# LVDS_UART.net
KiCad netlist of a schematic drawn in Altium Designer
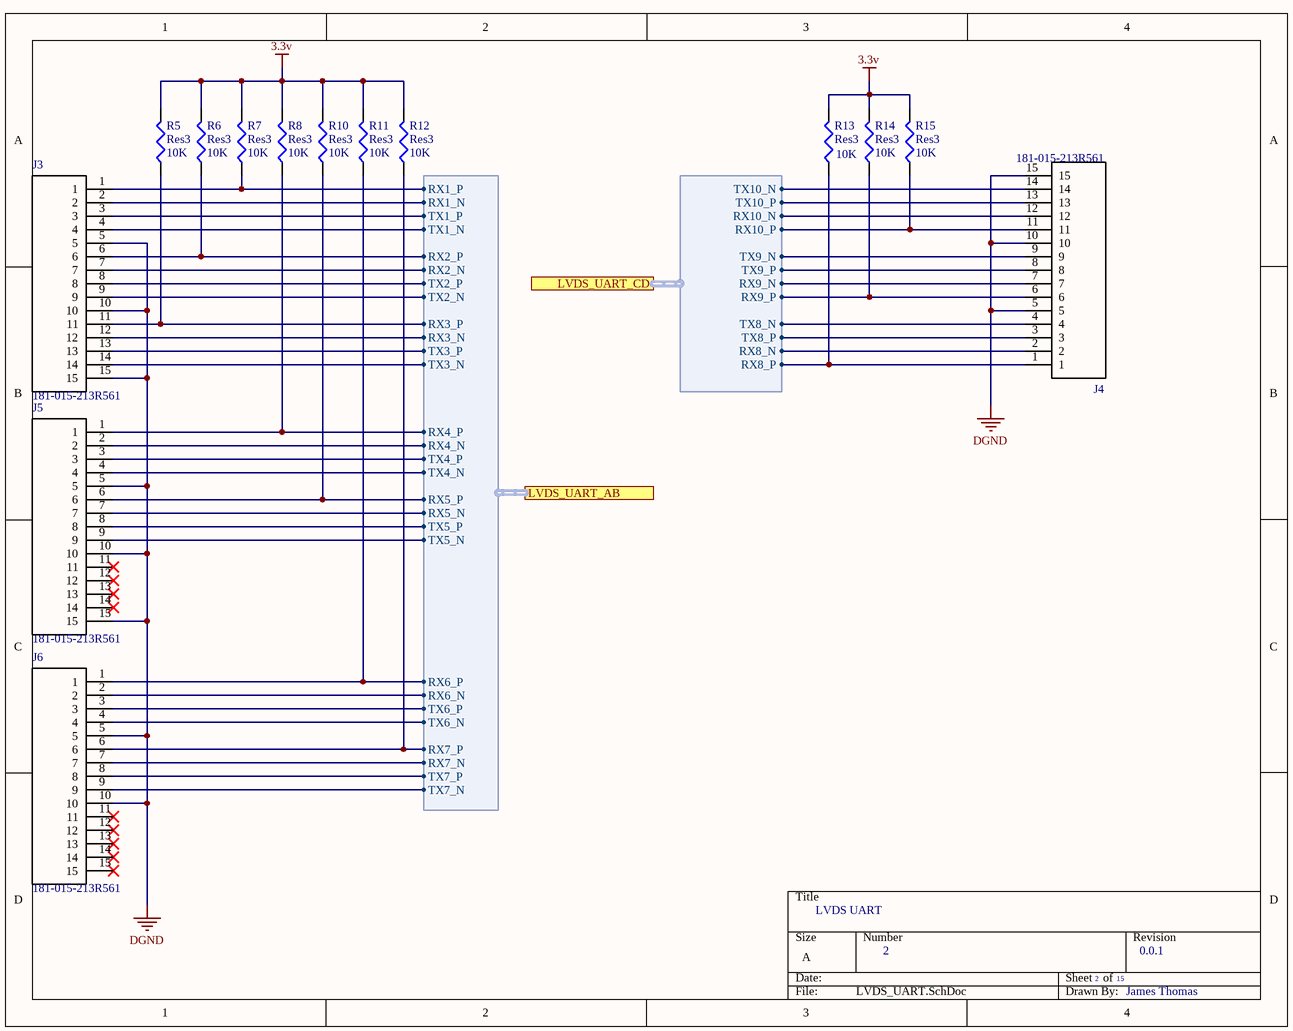
[diagram p0: LVDS_UART.SchDoc]

(export (version "E")
  (design (tool "Eeschema 10.0.6"))
  (components
    (comp (ref "J3")
      (value "181-015-213R561")
      (footprint "*NORCOMP_181-015-213R561")
      (description "15 Position D-Sub, High Density Receptacle, Female Sockets Connector")
      (fields (field (name "MF") "NorComp Inc."))
      (libsource (lib "Components") (part "181-015-213R561"))
    )
    (comp (ref "J4")
      (value "181-015-213R561")
      (footprint "*NORCOMP_181-015-213R561")
      (description "15 Position D-Sub, High Density Receptacle, Female Sockets Connector")
      (fields (field (name "MF") "NorComp Inc."))
      (libsource (lib "Components") (part "181-015-213R561"))
    )
    (comp (ref "J5")
      (value "181-015-213R561")
      (footprint "*NORCOMP_181-015-213R561")
      (description "15 Position D-Sub, High Density Receptacle, Female Sockets Connector")
      (fields (field (name "MF") "NorComp Inc."))
      (libsource (lib "Components") (part "181-015-213R561"))
    )
    (comp (ref "J6")
      (value "181-015-213R561")
      (footprint "*NORCOMP_181-015-213R561")
      (description "15 Position D-Sub, High Density Receptacle, Female Sockets Connector")
      (fields (field (name "MF") "NorComp Inc."))
      (libsource (lib "Components") (part "181-015-213R561"))
    )
    (comp (ref "R5")
      (value "Res3")
      (footprint "J1-0603")
      (description "Resistor")
      (fields (field (name "ALTIUM_VALUE") "10K") (field (name "PUBLISHER") "Altium Limited"))
      (libsource (lib "Miscellaneous Devices") (part "Res3"))
    )
    (comp (ref "R6")
      (value "Res3")
      (footprint "J1-0603")
      (description "Resistor")
      (fields (field (name "ALTIUM_VALUE") "10K") (field (name "PUBLISHER") "Altium Limited"))
      (libsource (lib "Miscellaneous Devices") (part "Res3"))
    )
    (comp (ref "R7")
      (value "Res3")
      (footprint "J1-0603")
      (description "Resistor")
      (fields (field (name "ALTIUM_VALUE") "10K") (field (name "PUBLISHER") "Altium Limited"))
      (libsource (lib "Miscellaneous Devices") (part "Res3"))
    )
    (comp (ref "R8")
      (value "Res3")
      (footprint "J1-0603")
      (description "Resistor")
      (fields (field (name "ALTIUM_VALUE") "10K") (field (name "PUBLISHER") "Altium Limited"))
      (libsource (lib "Miscellaneous Devices") (part "Res3"))
    )
    (comp (ref "R10")
      (value "Res3")
      (footprint "J1-0603")
      (description "Resistor")
      (fields (field (name "ALTIUM_VALUE") "10K") (field (name "PUBLISHER") "Altium Limited"))
      (libsource (lib "Miscellaneous Devices") (part "Res3"))
    )
    (comp (ref "R11")
      (value "Res3")
      (footprint "J1-0603")
      (description "Resistor")
      (fields (field (name "ALTIUM_VALUE") "10K") (field (name "PUBLISHER") "Altium Limited"))
      (libsource (lib "Miscellaneous Devices") (part "Res3"))
    )
    (comp (ref "R12")
      (value "Res3")
      (footprint "J1-0603")
      (description "Resistor")
      (fields (field (name "ALTIUM_VALUE") "10K") (field (name "PUBLISHER") "Altium Limited"))
      (libsource (lib "Miscellaneous Devices") (part "Res3"))
    )
    (comp (ref "R13")
      (value "Res3")
      (footprint "J1-0603")
      (description "Resistor")
      (fields (field (name "ALTIUM_VALUE") "10K") (field (name "PUBLISHER") "Altium Limited"))
      (libsource (lib "Miscellaneous Devices") (part "Res3"))
    )
    (comp (ref "R14")
      (value "Res3")
      (footprint "J1-0603")
      (description "Resistor")
      (fields (field (name "ALTIUM_VALUE") "10K") (field (name "PUBLISHER") "Altium Limited"))
      (libsource (lib "Miscellaneous Devices") (part "Res3"))
    )
    (comp (ref "R15")
      (value "Res3")
      (footprint "J1-0603")
      (description "Resistor")
      (fields (field (name "ALTIUM_VALUE") "10K") (field (name "PUBLISHER") "Altium Limited"))
      (libsource (lib "Miscellaneous Devices") (part "Res3"))
    )
  )
  (nets
    (net (code "3") (name "/RX1_N") (class "Default")
      (node (ref "J3") (pin "2") (pinfunction "2_2") (pintype "passive"))
    )
    (net (code "4") (name "/RX1_P") (class "Default")
      (node (ref "J3") (pin "1") (pinfunction "1_1") (pintype "passive"))
      (node (ref "R7") (pin "1") (pinfunction "1_1") (pintype "passive"))
    )
    (net (code "5") (name "/RX2_N") (class "Default")
      (node (ref "J3") (pin "7") (pinfunction "7_7") (pintype "passive"))
    )
    (net (code "6") (name "/RX2_P") (class "Default")
      (node (ref "J3") (pin "6") (pinfunction "6_6") (pintype "passive"))
      (node (ref "R6") (pin "1") (pinfunction "1_1") (pintype "passive"))
    )
    (net (code "7") (name "/RX3_N") (class "Default")
      (node (ref "J3") (pin "12") (pinfunction "12_12") (pintype "passive"))
    )
    (net (code "8") (name "/RX3_P") (class "Default")
      (node (ref "J3") (pin "11") (pinfunction "11_11") (pintype "passive"))
      (node (ref "R5") (pin "1") (pinfunction "1_1") (pintype "passive"))
    )
    (net (code "9") (name "/RX4_N") (class "Default")
      (node (ref "J5") (pin "2") (pinfunction "2_2") (pintype "passive"))
    )
    (net (code "10") (name "/RX4_P") (class "Default")
      (node (ref "J5") (pin "1") (pinfunction "1_1") (pintype "passive"))
      (node (ref "R8") (pin "1") (pinfunction "1_1") (pintype "passive"))
    )
    (net (code "11") (name "/RX5_N") (class "Default")
      (node (ref "J5") (pin "7") (pinfunction "7_7") (pintype "passive"))
    )
    (net (code "12") (name "/RX5_P") (class "Default")
      (node (ref "J5") (pin "6") (pinfunction "6_6") (pintype "passive"))
      (node (ref "R10") (pin "1") (pinfunction "1_1") (pintype "passive"))
    )
    (net (code "13") (name "/RX6_N") (class "Default")
      (node (ref "J6") (pin "2") (pinfunction "2_2") (pintype "passive"))
    )
    (net (code "14") (name "/RX6_P") (class "Default")
      (node (ref "J6") (pin "1") (pinfunction "1_1") (pintype "passive"))
      (node (ref "R11") (pin "1") (pinfunction "1_1") (pintype "passive"))
    )
    (net (code "15") (name "/RX7_N") (class "Default")
      (node (ref "J6") (pin "7") (pinfunction "7_7") (pintype "passive"))
    )
    (net (code "16") (name "/RX7_P") (class "Default")
      (node (ref "J6") (pin "6") (pinfunction "6_6") (pintype "passive"))
      (node (ref "R12") (pin "1") (pinfunction "1_1") (pintype "passive"))
    )
    (net (code "17") (name "/RX8_N") (class "Default")
      (node (ref "J4") (pin "2") (pinfunction "2_2") (pintype "passive"))
    )
    (net (code "18") (name "/RX8_P") (class "Default")
      (node (ref "J4") (pin "1") (pinfunction "1_1") (pintype "passive"))
      (node (ref "R13") (pin "1") (pinfunction "1_1") (pintype "passive"))
    )
    (net (code "19") (name "/RX9_N") (class "Default")
      (node (ref "J4") (pin "7") (pinfunction "7_7") (pintype "passive"))
    )
    (net (code "20") (name "/RX9_P") (class "Default")
      (node (ref "J4") (pin "6") (pinfunction "6_6") (pintype "passive"))
      (node (ref "R14") (pin "1") (pinfunction "1_1") (pintype "passive"))
    )
    (net (code "21") (name "/RX10_N") (class "Default")
      (node (ref "J4") (pin "12") (pinfunction "12_12") (pintype "passive"))
    )
    (net (code "22") (name "/RX10_P") (class "Default")
      (node (ref "J4") (pin "11") (pinfunction "11_11") (pintype "passive"))
      (node (ref "R15") (pin "1") (pinfunction "1_1") (pintype "passive"))
    )
    (net (code "23") (name "/TX1_N") (class "Default")
      (node (ref "J3") (pin "4") (pinfunction "4_4") (pintype "passive"))
    )
    (net (code "24") (name "/TX1_P") (class "Default")
      (node (ref "J3") (pin "3") (pinfunction "3_3") (pintype "passive"))
    )
    (net (code "25") (name "/TX2_N") (class "Default")
      (node (ref "J3") (pin "9") (pinfunction "9_9") (pintype "passive"))
    )
    (net (code "26") (name "/TX2_P") (class "Default")
      (node (ref "J3") (pin "8") (pinfunction "8_8") (pintype "passive"))
    )
    (net (code "27") (name "/TX3_N") (class "Default")
      (node (ref "J3") (pin "14") (pinfunction "14_14") (pintype "passive"))
    )
    (net (code "28") (name "/TX3_P") (class "Default")
      (node (ref "J3") (pin "13") (pinfunction "13_13") (pintype "passive"))
    )
    (net (code "29") (name "/TX4_N") (class "Default")
      (node (ref "J5") (pin "4") (pinfunction "4_4") (pintype "passive"))
    )
    (net (code "30") (name "/TX4_P") (class "Default")
      (node (ref "J5") (pin "3") (pinfunction "3_3") (pintype "passive"))
    )
    (net (code "31") (name "/TX5_N") (class "Default")
      (node (ref "J5") (pin "9") (pinfunction "9_9") (pintype "passive"))
    )
    (net (code "32") (name "/TX5_P") (class "Default")
      (node (ref "J5") (pin "8") (pinfunction "8_8") (pintype "passive"))
    )
    (net (code "33") (name "/TX6_N") (class "Default")
      (node (ref "J6") (pin "4") (pinfunction "4_4") (pintype "passive"))
    )
    (net (code "34") (name "/TX6_P") (class "Default")
      (node (ref "J6") (pin "3") (pinfunction "3_3") (pintype "passive"))
    )
    (net (code "35") (name "/TX7_N") (class "Default")
      (node (ref "J6") (pin "9") (pinfunction "9_9") (pintype "passive"))
    )
    (net (code "36") (name "/TX7_P") (class "Default")
      (node (ref "J6") (pin "8") (pinfunction "8_8") (pintype "passive"))
    )
    (net (code "37") (name "/TX8_N") (class "Default")
      (node (ref "J4") (pin "4") (pinfunction "4_4") (pintype "passive"))
    )
    (net (code "38") (name "/TX8_P") (class "Default")
      (node (ref "J4") (pin "3") (pinfunction "3_3") (pintype "passive"))
    )
    (net (code "39") (name "/TX9_N") (class "Default")
      (node (ref "J4") (pin "9") (pinfunction "9_9") (pintype "passive"))
    )
    (net (code "40") (name "/TX9_P") (class "Default")
      (node (ref "J4") (pin "8") (pinfunction "8_8") (pintype "passive"))
    )
    (net (code "41") (name "/TX10_N") (class "Default")
      (node (ref "J4") (pin "14") (pinfunction "14_14") (pintype "passive"))
    )
    (net (code "42") (name "/TX10_P") (class "Default")
      (node (ref "J4") (pin "13") (pinfunction "13_13") (pintype "passive"))
    )
    (net (code "45") (name "3.3v") (class "Default")
      (node (ref "R10") (pin "2") (pinfunction "2_2") (pintype "passive"))
      (node (ref "R11") (pin "2") (pinfunction "2_2") (pintype "passive"))
      (node (ref "R12") (pin "2") (pinfunction "2_2") (pintype "passive"))
      (node (ref "R13") (pin "2") (pinfunction "2_2") (pintype "passive"))
      (node (ref "R14") (pin "2") (pinfunction "2_2") (pintype "passive"))
      (node (ref "R15") (pin "2") (pinfunction "2_2") (pintype "passive"))
      (node (ref "R5") (pin "2") (pinfunction "2_2") (pintype "passive"))
      (node (ref "R6") (pin "2") (pinfunction "2_2") (pintype "passive"))
      (node (ref "R7") (pin "2") (pinfunction "2_2") (pintype "passive"))
      (node (ref "R8") (pin "2") (pinfunction "2_2") (pintype "passive"))
    )
    (net (code "46") (name "DGND") (class "Default")
      (node (ref "J3") (pin "10") (pinfunction "10_10") (pintype "passive"))
      (node (ref "J3") (pin "15") (pinfunction "15_15") (pintype "passive"))
      (node (ref "J3") (pin "5") (pinfunction "5_5") (pintype "passive"))
      (node (ref "J4") (pin "10") (pinfunction "10_10") (pintype "passive"))
      (node (ref "J4") (pin "15") (pinfunction "15_15") (pintype "passive"))
      (node (ref "J4") (pin "5") (pinfunction "5_5") (pintype "passive"))
      (node (ref "J5") (pin "10") (pinfunction "10_10") (pintype "passive"))
      (node (ref "J5") (pin "15") (pinfunction "15_15") (pintype "passive"))
      (node (ref "J5") (pin "5") (pinfunction "5_5") (pintype "passive"))
      (node (ref "J6") (pin "10") (pinfunction "10_10") (pintype "passive"))
      (node (ref "J6") (pin "5") (pinfunction "5_5") (pintype "passive"))
    )
    (net (code "47") (name "unconnected-(J5-Pad11)") (class "Default")
      (node (ref "J5") (pin "11") (pinfunction "11_11") (pintype "passive+no_connect"))
    )
    (net (code "48") (name "unconnected-(J5-Pad12)") (class "Default")
      (node (ref "J5") (pin "12") (pinfunction "12_12") (pintype "passive+no_connect"))
    )
    (net (code "49") (name "unconnected-(J5-Pad13)") (class "Default")
      (node (ref "J5") (pin "13") (pinfunction "13_13") (pintype "passive+no_connect"))
    )
    (net (code "50") (name "unconnected-(J5-Pad14)") (class "Default")
      (node (ref "J5") (pin "14") (pinfunction "14_14") (pintype "passive+no_connect"))
    )
    (net (code "51") (name "unconnected-(J6-Pad11)") (class "Default")
      (node (ref "J6") (pin "11") (pinfunction "11_11") (pintype "passive+no_connect"))
    )
    (net (code "52") (name "unconnected-(J6-Pad12)") (class "Default")
      (node (ref "J6") (pin "12") (pinfunction "12_12") (pintype "passive+no_connect"))
    )
    (net (code "53") (name "unconnected-(J6-Pad13)") (class "Default")
      (node (ref "J6") (pin "13") (pinfunction "13_13") (pintype "passive+no_connect"))
    )
    (net (code "54") (name "unconnected-(J6-Pad14)") (class "Default")
      (node (ref "J6") (pin "14") (pinfunction "14_14") (pintype "passive+no_connect"))
    )
    (net (code "55") (name "unconnected-(J6-Pad15)") (class "Default")
      (node (ref "J6") (pin "15") (pinfunction "15_15") (pintype "passive+no_connect"))
    )
  )
)
